# BTN.net
KiCad netlist of a schematic drawn in Altium Designer
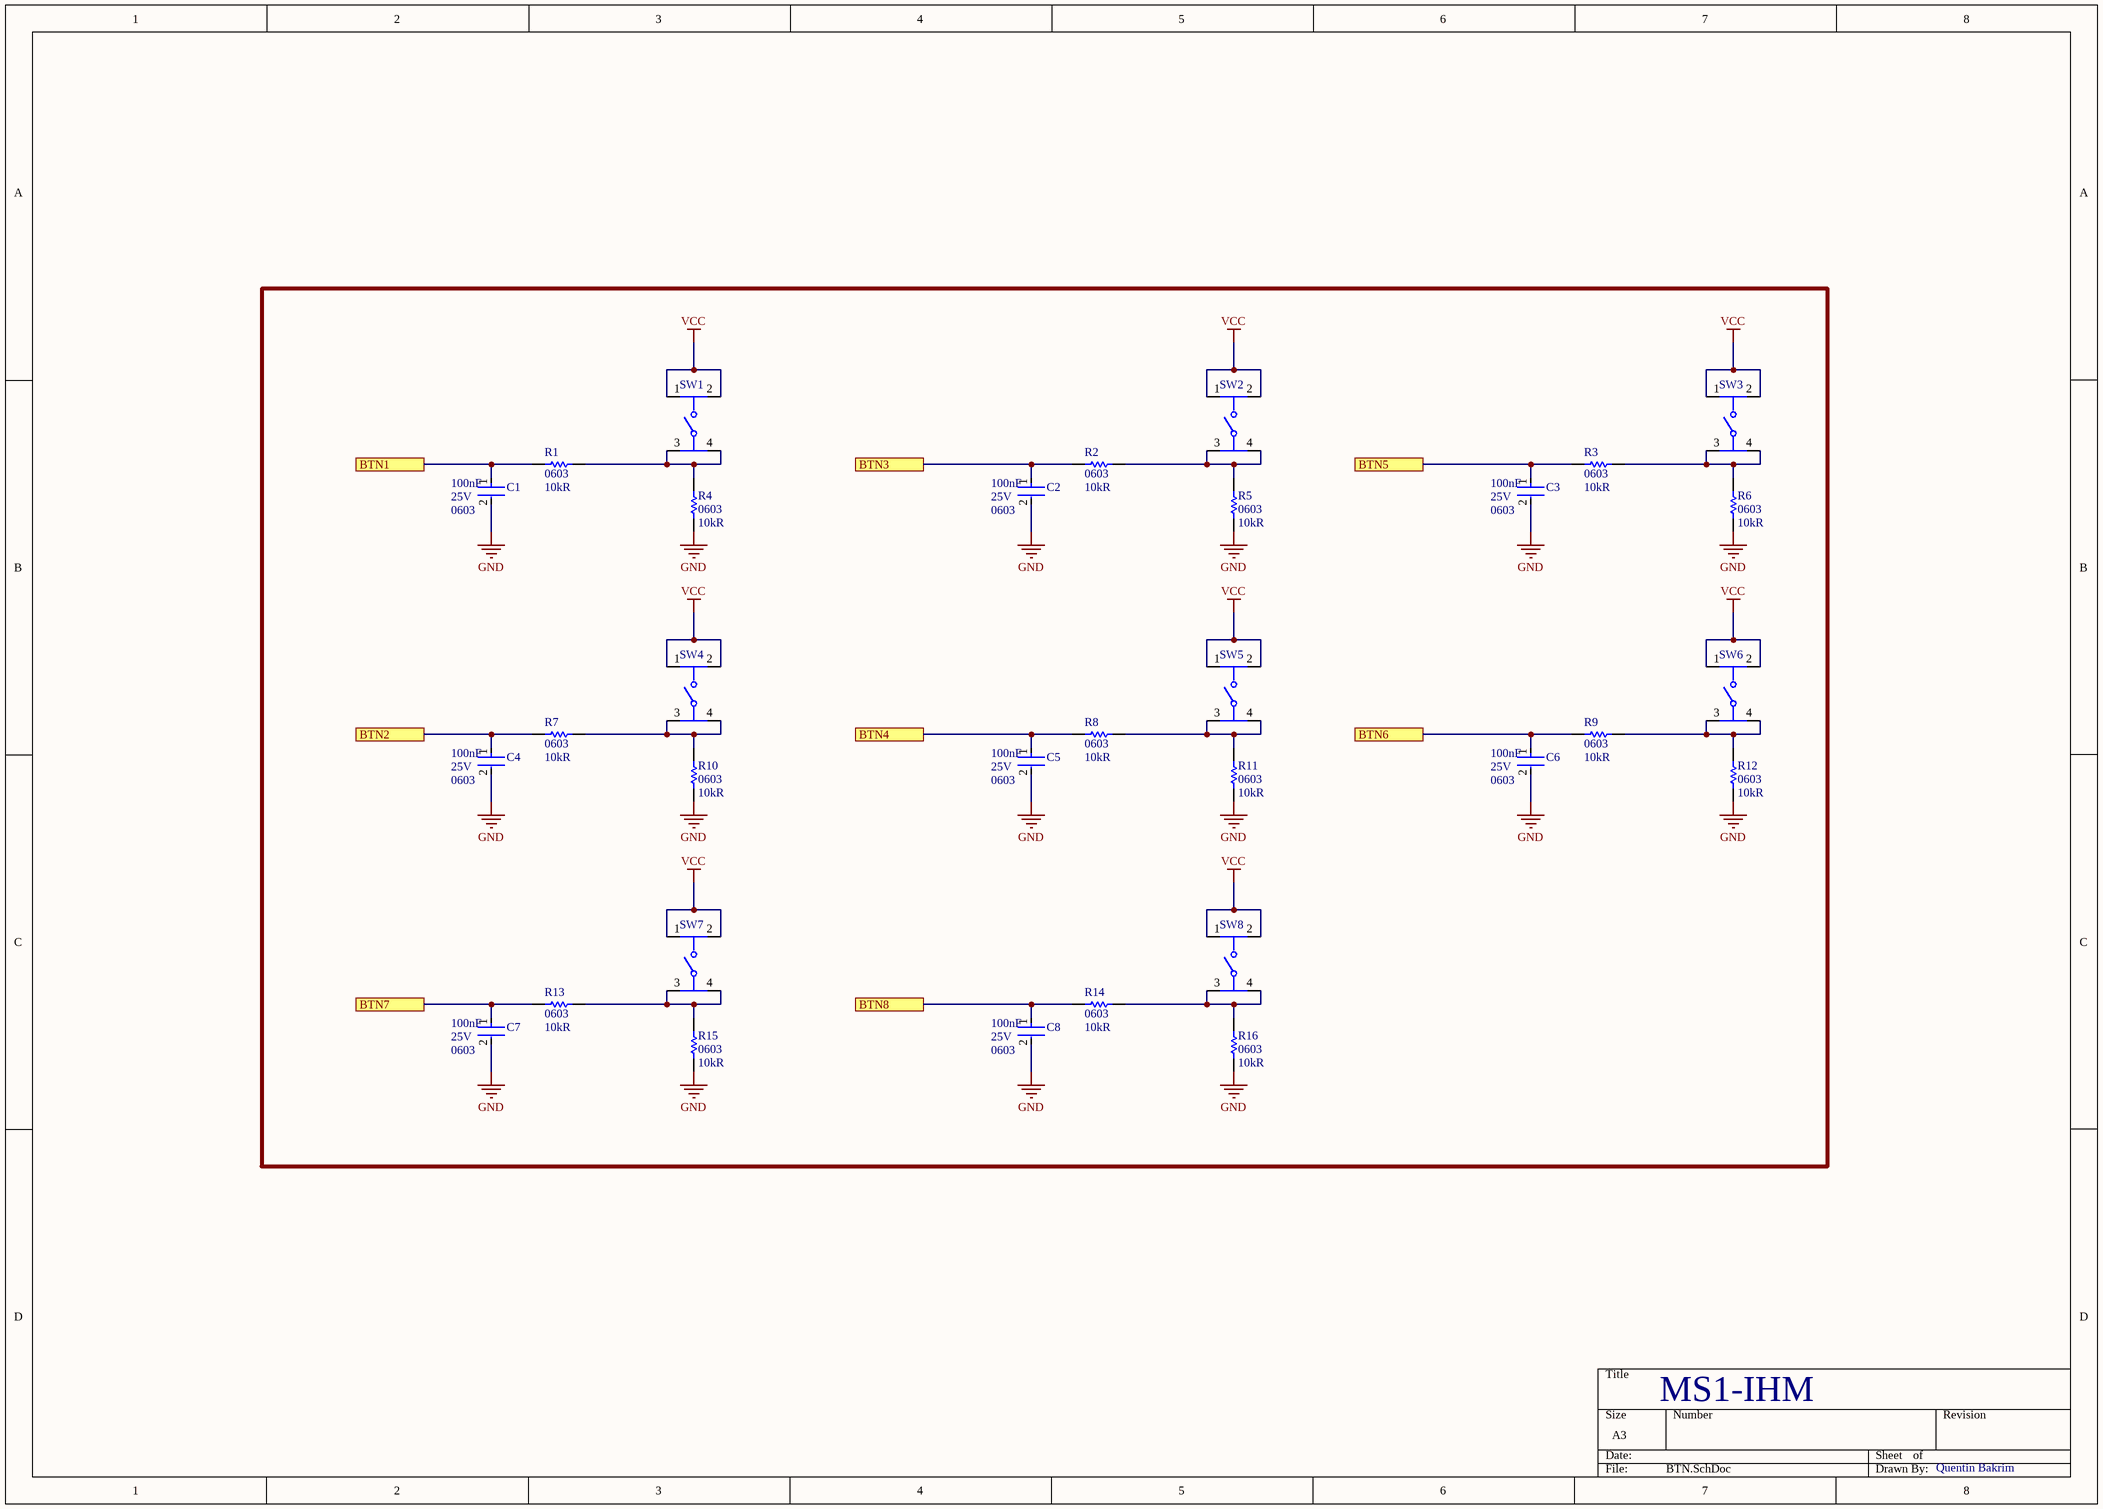
[diagram p0: BTN.SchDoc]

(export (version "E")
  (design (tool "Eeschema 10.0.6"))
  (components
    (comp (ref "C1")
      (value "CGA3E2X7R1E104K080AA")
      (footprint "FP-CGA3E-0_3-0_1-MFG")
      (description "Cap Ceramic 100nF 25V X7R 10% Pad SMD 0603 +125°C Automotive T/R")
      (fields
        (field (name "CASE/PACKAGE") "0603")
        (field (name "VOLTAGE RATING (DC)") "25V")
        (field (name "CAPACITANCE") "100nF")
        (field (name "TOLERANCE") "10%")
        (field (name "MANUFACTURER") "TDK")
      )
      (libsource (lib "Altium Content Vault") (part "b4654b650e69147ec39a6b967a45e02"))
    )
    (comp (ref "C2")
      (value "CGA3E2X7R1E104K080AA")
      (footprint "FP-CGA3E-0_3-0_1-MFG")
      (description "Cap Ceramic 100nF 25V X7R 10% Pad SMD 0603 +125°C Automotive T/R")
      (fields
        (field (name "CASE/PACKAGE") "0603")
        (field (name "VOLTAGE RATING (DC)") "25V")
        (field (name "CAPACITANCE") "100nF")
        (field (name "TOLERANCE") "10%")
        (field (name "MANUFACTURER") "TDK")
      )
      (libsource (lib "Altium Content Vault") (part "b4654b650e69147ec39a6b967a45e02"))
    )
    (comp (ref "C3")
      (value "CGA3E2X7R1E104K080AA")
      (footprint "FP-CGA3E-0_3-0_1-MFG")
      (description "Cap Ceramic 100nF 25V X7R 10% Pad SMD 0603 +125°C Automotive T/R")
      (fields
        (field (name "CASE/PACKAGE") "0603")
        (field (name "VOLTAGE RATING (DC)") "25V")
        (field (name "CAPACITANCE") "100nF")
        (field (name "TOLERANCE") "10%")
        (field (name "MANUFACTURER") "TDK")
      )
      (libsource (lib "Altium Content Vault") (part "b4654b650e69147ec39a6b967a45e02"))
    )
    (comp (ref "C4")
      (value "CGA3E2X7R1E104K080AA")
      (footprint "FP-CGA3E-0_3-0_1-MFG")
      (description "Cap Ceramic 100nF 25V X7R 10% Pad SMD 0603 +125°C Automotive T/R")
      (fields
        (field (name "CASE/PACKAGE") "0603")
        (field (name "VOLTAGE RATING (DC)") "25V")
        (field (name "CAPACITANCE") "100nF")
        (field (name "TOLERANCE") "10%")
        (field (name "MANUFACTURER") "TDK")
      )
      (libsource (lib "Altium Content Vault") (part "b4654b650e69147ec39a6b967a45e02"))
    )
    (comp (ref "C5")
      (value "CGA3E2X7R1E104K080AA")
      (footprint "FP-CGA3E-0_3-0_1-MFG")
      (description "Cap Ceramic 100nF 25V X7R 10% Pad SMD 0603 +125°C Automotive T/R")
      (fields
        (field (name "CASE/PACKAGE") "0603")
        (field (name "VOLTAGE RATING (DC)") "25V")
        (field (name "CAPACITANCE") "100nF")
        (field (name "TOLERANCE") "10%")
        (field (name "MANUFACTURER") "TDK")
      )
      (libsource (lib "Altium Content Vault") (part "b4654b650e69147ec39a6b967a45e02"))
    )
    (comp (ref "C6")
      (value "CGA3E2X7R1E104K080AA")
      (footprint "FP-CGA3E-0_3-0_1-MFG")
      (description "Cap Ceramic 100nF 25V X7R 10% Pad SMD 0603 +125°C Automotive T/R")
      (fields
        (field (name "CASE/PACKAGE") "0603")
        (field (name "VOLTAGE RATING (DC)") "25V")
        (field (name "CAPACITANCE") "100nF")
        (field (name "TOLERANCE") "10%")
        (field (name "MANUFACTURER") "TDK")
      )
      (libsource (lib "Altium Content Vault") (part "b4654b650e69147ec39a6b967a45e02"))
    )
    (comp (ref "C7")
      (value "CGA3E2X7R1E104K080AA")
      (footprint "FP-CGA3E-0_3-0_1-MFG")
      (description "Cap Ceramic 100nF 25V X7R 10% Pad SMD 0603 +125°C Automotive T/R")
      (fields
        (field (name "CASE/PACKAGE") "0603")
        (field (name "VOLTAGE RATING (DC)") "25V")
        (field (name "CAPACITANCE") "100nF")
        (field (name "TOLERANCE") "10%")
        (field (name "MANUFACTURER") "TDK")
      )
      (libsource (lib "Altium Content Vault") (part "b4654b650e69147ec39a6b967a45e02"))
    )
    (comp (ref "C8")
      (value "CGA3E2X7R1E104K080AA")
      (footprint "FP-CGA3E-0_3-0_1-MFG")
      (description "Cap Ceramic 100nF 25V X7R 10% Pad SMD 0603 +125°C Automotive T/R")
      (fields
        (field (name "CASE/PACKAGE") "0603")
        (field (name "VOLTAGE RATING (DC)") "25V")
        (field (name "CAPACITANCE") "100nF")
        (field (name "TOLERANCE") "10%")
        (field (name "MANUFACTURER") "TDK")
      )
      (libsource (lib "Altium Content Vault") (part "b4654b650e69147ec39a6b967a45e02"))
    )
    (comp (ref "R1")
      (value "ERJ3EKF1002V")
      (footprint "RESC1609X55X30LL15T15")
      (description "Chip Resistor, 10 KOhm, +/- 1%, 0.1 W, -55 to 155 degC, 0603 (1608 Metric), RoHS, Tape and Reel")
      (fields
        (field (name "CAS~{E}/PACKAGE") "0603")
        (field (name "RESISTANCE") "10kR")
        (field (name "TOLERANCE") "1%")
        (field (name "MANUFACTURER") "Panasonic")
      )
      (libsource (lib "Altium Content Vault") (part "RES-2"))
    )
    (comp (ref "R2")
      (value "ERJ3EKF1002V")
      (footprint "RESC1609X55X30LL15T15")
      (description "Chip Resistor, 10 KOhm, +/- 1%, 0.1 W, -55 to 155 degC, 0603 (1608 Metric), RoHS, Tape and Reel")
      (fields
        (field (name "CAS~{E}/PACKAGE") "0603")
        (field (name "RESISTANCE") "10kR")
        (field (name "TOLERANCE") "1%")
        (field (name "MANUFACTURER") "Panasonic")
      )
      (libsource (lib "Altium Content Vault") (part "RES-2"))
    )
    (comp (ref "R3")
      (value "ERJ3EKF1002V")
      (footprint "RESC1609X55X30LL15T15")
      (description "Chip Resistor, 10 KOhm, +/- 1%, 0.1 W, -55 to 155 degC, 0603 (1608 Metric), RoHS, Tape and Reel")
      (fields
        (field (name "CAS~{E}/PACKAGE") "0603")
        (field (name "RESISTANCE") "10kR")
        (field (name "TOLERANCE") "1%")
        (field (name "MANUFACTURER") "Panasonic")
      )
      (libsource (lib "Altium Content Vault") (part "RES-2"))
    )
    (comp (ref "R4")
      (value "ERJ3EKF1002V")
      (footprint "RESC1609X55X30LL15T15")
      (description "Chip Resistor, 10 KOhm, +/- 1%, 0.1 W, -55 to 155 degC, 0603 (1608 Metric), RoHS, Tape and Reel")
      (fields
        (field (name "CAS~{E}/PACKAGE") "0603")
        (field (name "RESISTANCE") "10kR")
        (field (name "TOLERANCE") "1%")
        (field (name "MANUFACTURER") "Panasonic")
      )
      (libsource (lib "Altium Content Vault") (part "RES-2"))
    )
    (comp (ref "R5")
      (value "ERJ3EKF1002V")
      (footprint "RESC1609X55X30LL15T15")
      (description "Chip Resistor, 10 KOhm, +/- 1%, 0.1 W, -55 to 155 degC, 0603 (1608 Metric), RoHS, Tape and Reel")
      (fields
        (field (name "CAS~{E}/PACKAGE") "0603")
        (field (name "RESISTANCE") "10kR")
        (field (name "TOLERANCE") "1%")
        (field (name "MANUFACTURER") "Panasonic")
      )
      (libsource (lib "Altium Content Vault") (part "RES-2"))
    )
    (comp (ref "R6")
      (value "ERJ3EKF1002V")
      (footprint "RESC1609X55X30LL15T15")
      (description "Chip Resistor, 10 KOhm, +/- 1%, 0.1 W, -55 to 155 degC, 0603 (1608 Metric), RoHS, Tape and Reel")
      (fields
        (field (name "CAS~{E}/PACKAGE") "0603")
        (field (name "RESISTANCE") "10kR")
        (field (name "TOLERANCE") "1%")
        (field (name "MANUFACTURER") "Panasonic")
      )
      (libsource (lib "Altium Content Vault") (part "RES-2"))
    )
    (comp (ref "R7")
      (value "ERJ3EKF1002V")
      (footprint "RESC1609X55X30LL15T15")
      (description "Chip Resistor, 10 KOhm, +/- 1%, 0.1 W, -55 to 155 degC, 0603 (1608 Metric), RoHS, Tape and Reel")
      (fields
        (field (name "CAS~{E}/PACKAGE") "0603")
        (field (name "RESISTANCE") "10kR")
        (field (name "TOLERANCE") "1%")
        (field (name "MANUFACTURER") "Panasonic")
      )
      (libsource (lib "Altium Content Vault") (part "RES-2"))
    )
    (comp (ref "R8")
      (value "ERJ3EKF1002V")
      (footprint "RESC1609X55X30LL15T15")
      (description "Chip Resistor, 10 KOhm, +/- 1%, 0.1 W, -55 to 155 degC, 0603 (1608 Metric), RoHS, Tape and Reel")
      (fields
        (field (name "CAS~{E}/PACKAGE") "0603")
        (field (name "RESISTANCE") "10kR")
        (field (name "TOLERANCE") "1%")
        (field (name "MANUFACTURER") "Panasonic")
      )
      (libsource (lib "Altium Content Vault") (part "RES-2"))
    )
    (comp (ref "R9")
      (value "ERJ3EKF1002V")
      (footprint "RESC1609X55X30LL15T15")
      (description "Chip Resistor, 10 KOhm, +/- 1%, 0.1 W, -55 to 155 degC, 0603 (1608 Metric), RoHS, Tape and Reel")
      (fields
        (field (name "CAS~{E}/PACKAGE") "0603")
        (field (name "RESISTANCE") "10kR")
        (field (name "TOLERANCE") "1%")
        (field (name "MANUFACTURER") "Panasonic")
      )
      (libsource (lib "Altium Content Vault") (part "RES-2"))
    )
    (comp (ref "R10")
      (value "ERJ3EKF1002V")
      (footprint "RESC1609X55X30LL15T15")
      (description "Chip Resistor, 10 KOhm, +/- 1%, 0.1 W, -55 to 155 degC, 0603 (1608 Metric), RoHS, Tape and Reel")
      (fields
        (field (name "CAS~{E}/PACKAGE") "0603")
        (field (name "RESISTANCE") "10kR")
        (field (name "TOLERANCE") "1%")
        (field (name "MANUFACTURER") "Panasonic")
      )
      (libsource (lib "Altium Content Vault") (part "RES-2"))
    )
    (comp (ref "R11")
      (value "ERJ3EKF1002V")
      (footprint "RESC1609X55X30LL15T15")
      (description "Chip Resistor, 10 KOhm, +/- 1%, 0.1 W, -55 to 155 degC, 0603 (1608 Metric), RoHS, Tape and Reel")
      (fields
        (field (name "CAS~{E}/PACKAGE") "0603")
        (field (name "RESISTANCE") "10kR")
        (field (name "TOLERANCE") "1%")
        (field (name "MANUFACTURER") "Panasonic")
      )
      (libsource (lib "Altium Content Vault") (part "RES-2"))
    )
    (comp (ref "R12")
      (value "ERJ3EKF1002V")
      (footprint "RESC1609X55X30LL15T15")
      (description "Chip Resistor, 10 KOhm, +/- 1%, 0.1 W, -55 to 155 degC, 0603 (1608 Metric), RoHS, Tape and Reel")
      (fields
        (field (name "CAS~{E}/PACKAGE") "0603")
        (field (name "RESISTANCE") "10kR")
        (field (name "TOLERANCE") "1%")
        (field (name "MANUFACTURER") "Panasonic")
      )
      (libsource (lib "Altium Content Vault") (part "RES-2"))
    )
    (comp (ref "R13")
      (value "ERJ3EKF1002V")
      (footprint "RESC1609X55X30LL15T15")
      (description "Chip Resistor, 10 KOhm, +/- 1%, 0.1 W, -55 to 155 degC, 0603 (1608 Metric), RoHS, Tape and Reel")
      (fields
        (field (name "CAS~{E}/PACKAGE") "0603")
        (field (name "RESISTANCE") "10kR")
        (field (name "TOLERANCE") "1%")
        (field (name "MANUFACTURER") "Panasonic")
      )
      (libsource (lib "Altium Content Vault") (part "RES-2"))
    )
    (comp (ref "R14")
      (value "ERJ3EKF1002V")
      (footprint "RESC1609X55X30LL15T15")
      (description "Chip Resistor, 10 KOhm, +/- 1%, 0.1 W, -55 to 155 degC, 0603 (1608 Metric), RoHS, Tape and Reel")
      (fields
        (field (name "CAS~{E}/PACKAGE") "0603")
        (field (name "RESISTANCE") "10kR")
        (field (name "TOLERANCE") "1%")
        (field (name "MANUFACTURER") "Panasonic")
      )
      (libsource (lib "Altium Content Vault") (part "RES-2"))
    )
    (comp (ref "R15")
      (value "ERJ3EKF1002V")
      (footprint "RESC1609X55X30LL15T15")
      (description "Chip Resistor, 10 KOhm, +/- 1%, 0.1 W, -55 to 155 degC, 0603 (1608 Metric), RoHS, Tape and Reel")
      (fields
        (field (name "CAS~{E}/PACKAGE") "0603")
        (field (name "RESISTANCE") "10kR")
        (field (name "TOLERANCE") "1%")
        (field (name "MANUFACTURER") "Panasonic")
      )
      (libsource (lib "Altium Content Vault") (part "RES-2"))
    )
    (comp (ref "R16")
      (value "ERJ3EKF1002V")
      (footprint "RESC1609X55X30LL15T15")
      (description "Chip Resistor, 10 KOhm, +/- 1%, 0.1 W, -55 to 155 degC, 0603 (1608 Metric), RoHS, Tape and Reel")
      (fields
        (field (name "CAS~{E}/PACKAGE") "0603")
        (field (name "RESISTANCE") "10kR")
        (field (name "TOLERANCE") "1%")
        (field (name "MANUFACTURER") "Panasonic")
      )
      (libsource (lib "Altium Content Vault") (part "RES-2"))
    )
    (comp (ref "SW1")
      (value "PTS645SM43SMTR92LFS")
      (footprint "FP-PTS645SM43SMTR92LFS-MFG")
      (libsource (lib "Altium Content Vault") (part "1adf0dd01260c80cf25a44bfd6b99ba"))
    )
    (comp (ref "SW2")
      (value "PTS645SM43SMTR92LFS")
      (footprint "FP-PTS645SM43SMTR92LFS-MFG")
      (libsource (lib "Altium Content Vault") (part "1adf0dd01260c80cf25a44bfd6b99ba"))
    )
    (comp (ref "SW3")
      (value "PTS645SM43SMTR92LFS")
      (footprint "FP-PTS645SM43SMTR92LFS-MFG")
      (libsource (lib "Altium Content Vault") (part "1adf0dd01260c80cf25a44bfd6b99ba"))
    )
    (comp (ref "SW4")
      (value "PTS645SM43SMTR92LFS")
      (footprint "FP-PTS645SM43SMTR92LFS-MFG")
      (libsource (lib "Altium Content Vault") (part "1adf0dd01260c80cf25a44bfd6b99ba"))
    )
    (comp (ref "SW5")
      (value "PTS645SM43SMTR92LFS")
      (footprint "FP-PTS645SM43SMTR92LFS-MFG")
      (libsource (lib "Altium Content Vault") (part "1adf0dd01260c80cf25a44bfd6b99ba"))
    )
    (comp (ref "SW6")
      (value "PTS645SM43SMTR92LFS")
      (footprint "FP-PTS645SM43SMTR92LFS-MFG")
      (libsource (lib "Altium Content Vault") (part "1adf0dd01260c80cf25a44bfd6b99ba"))
    )
    (comp (ref "SW7")
      (value "PTS645SM43SMTR92LFS")
      (footprint "FP-PTS645SM43SMTR92LFS-MFG")
      (libsource (lib "Altium Content Vault") (part "1adf0dd01260c80cf25a44bfd6b99ba"))
    )
    (comp (ref "SW8")
      (value "PTS645SM43SMTR92LFS")
      (footprint "FP-PTS645SM43SMTR92LFS-MFG")
      (libsource (lib "Altium Content Vault") (part "1adf0dd01260c80cf25a44bfd6b99ba"))
    )
  )
  (nets
    (net (code "1") (name "/BTN1") (class "Default")
      (node (ref "C1") (pin "1") (pinfunction "1_1") (pintype "passive"))
      (node (ref "R1") (pin "2") (pinfunction "2_2") (pintype "passive"))
    )
    (net (code "2") (name "/BTN2") (class "Default")
      (node (ref "C4") (pin "1") (pinfunction "1_1") (pintype "passive"))
      (node (ref "R7") (pin "2") (pinfunction "2_2") (pintype "passive"))
    )
    (net (code "3") (name "/BTN3") (class "Default")
      (node (ref "C2") (pin "1") (pinfunction "1_1") (pintype "passive"))
      (node (ref "R2") (pin "2") (pinfunction "2_2") (pintype "passive"))
    )
    (net (code "4") (name "/BTN4") (class "Default")
      (node (ref "C5") (pin "1") (pinfunction "1_1") (pintype "passive"))
      (node (ref "R8") (pin "2") (pinfunction "2_2") (pintype "passive"))
    )
    (net (code "5") (name "/BTN5") (class "Default")
      (node (ref "C3") (pin "1") (pinfunction "1_1") (pintype "passive"))
      (node (ref "R3") (pin "2") (pinfunction "2_2") (pintype "passive"))
    )
    (net (code "6") (name "/BTN6") (class "Default")
      (node (ref "C6") (pin "1") (pinfunction "1_1") (pintype "passive"))
      (node (ref "R9") (pin "2") (pinfunction "2_2") (pintype "passive"))
    )
    (net (code "7") (name "/BTN7") (class "Default")
      (node (ref "C7") (pin "1") (pinfunction "1_1") (pintype "passive"))
      (node (ref "R13") (pin "2") (pinfunction "2_2") (pintype "passive"))
    )
    (net (code "8") (name "/BTN8") (class "Default")
      (node (ref "C8") (pin "1") (pinfunction "1_1") (pintype "passive"))
      (node (ref "R14") (pin "2") (pinfunction "2_2") (pintype "passive"))
    )
    (net (code "9") (name "GND") (class "Default")
      (node (ref "C1") (pin "2") (pinfunction "2_2") (pintype "passive"))
      (node (ref "C2") (pin "2") (pinfunction "2_2") (pintype "passive"))
      (node (ref "C3") (pin "2") (pinfunction "2_2") (pintype "passive"))
      (node (ref "C4") (pin "2") (pinfunction "2_2") (pintype "passive"))
      (node (ref "C5") (pin "2") (pinfunction "2_2") (pintype "passive"))
      (node (ref "C6") (pin "2") (pinfunction "2_2") (pintype "passive"))
      (node (ref "C7") (pin "2") (pinfunction "2_2") (pintype "passive"))
      (node (ref "C8") (pin "2") (pinfunction "2_2") (pintype "passive"))
      (node (ref "R10") (pin "1") (pinfunction "1_1") (pintype "passive"))
      (node (ref "R11") (pin "1") (pinfunction "1_1") (pintype "passive"))
      (node (ref "R12") (pin "1") (pinfunction "1_1") (pintype "passive"))
      (node (ref "R15") (pin "1") (pinfunction "1_1") (pintype "passive"))
      (node (ref "R16") (pin "1") (pinfunction "1_1") (pintype "passive"))
      (node (ref "R4") (pin "1") (pinfunction "1_1") (pintype "passive"))
      (node (ref "R5") (pin "1") (pinfunction "1_1") (pintype "passive"))
      (node (ref "R6") (pin "1") (pinfunction "1_1") (pintype "passive"))
    )
    (net (code "10") (name "Net-(R1-Pad1)") (class "Default")
      (node (ref "R1") (pin "1") (pinfunction "1_1") (pintype "passive"))
      (node (ref "R4") (pin "2") (pinfunction "2_2") (pintype "passive"))
      (node (ref "SW1") (pin "3") (pinfunction "3_3") (pintype "passive"))
      (node (ref "SW1") (pin "4") (pinfunction "4_4") (pintype "passive"))
    )
    (net (code "11") (name "Net-(R2-Pad1)") (class "Default")
      (node (ref "R2") (pin "1") (pinfunction "1_1") (pintype "passive"))
      (node (ref "R5") (pin "2") (pinfunction "2_2") (pintype "passive"))
      (node (ref "SW2") (pin "3") (pinfunction "3_3") (pintype "passive"))
      (node (ref "SW2") (pin "4") (pinfunction "4_4") (pintype "passive"))
    )
    (net (code "12") (name "Net-(R3-Pad1)") (class "Default")
      (node (ref "R3") (pin "1") (pinfunction "1_1") (pintype "passive"))
      (node (ref "R6") (pin "2") (pinfunction "2_2") (pintype "passive"))
      (node (ref "SW3") (pin "3") (pinfunction "3_3") (pintype "passive"))
      (node (ref "SW3") (pin "4") (pinfunction "4_4") (pintype "passive"))
    )
    (net (code "13") (name "Net-(R10-Pad2)") (class "Default")
      (node (ref "R10") (pin "2") (pinfunction "2_2") (pintype "passive"))
      (node (ref "R7") (pin "1") (pinfunction "1_1") (pintype "passive"))
      (node (ref "SW4") (pin "3") (pinfunction "3_3") (pintype "passive"))
      (node (ref "SW4") (pin "4") (pinfunction "4_4") (pintype "passive"))
    )
    (net (code "14") (name "Net-(R11-Pad2)") (class "Default")
      (node (ref "R11") (pin "2") (pinfunction "2_2") (pintype "passive"))
      (node (ref "R8") (pin "1") (pinfunction "1_1") (pintype "passive"))
      (node (ref "SW5") (pin "3") (pinfunction "3_3") (pintype "passive"))
      (node (ref "SW5") (pin "4") (pinfunction "4_4") (pintype "passive"))
    )
    (net (code "15") (name "Net-(R12-Pad2)") (class "Default")
      (node (ref "R12") (pin "2") (pinfunction "2_2") (pintype "passive"))
      (node (ref "R9") (pin "1") (pinfunction "1_1") (pintype "passive"))
      (node (ref "SW6") (pin "3") (pinfunction "3_3") (pintype "passive"))
      (node (ref "SW6") (pin "4") (pinfunction "4_4") (pintype "passive"))
    )
    (net (code "16") (name "Net-(R13-Pad1)") (class "Default")
      (node (ref "R13") (pin "1") (pinfunction "1_1") (pintype "passive"))
      (node (ref "R15") (pin "2") (pinfunction "2_2") (pintype "passive"))
      (node (ref "SW7") (pin "3") (pinfunction "3_3") (pintype "passive"))
      (node (ref "SW7") (pin "4") (pinfunction "4_4") (pintype "passive"))
    )
    (net (code "17") (name "Net-(R14-Pad1)") (class "Default")
      (node (ref "R14") (pin "1") (pinfunction "1_1") (pintype "passive"))
      (node (ref "R16") (pin "2") (pinfunction "2_2") (pintype "passive"))
      (node (ref "SW8") (pin "3") (pinfunction "3_3") (pintype "passive"))
      (node (ref "SW8") (pin "4") (pinfunction "4_4") (pintype "passive"))
    )
    (net (code "18") (name "VCC") (class "Default")
      (node (ref "SW1") (pin "1") (pinfunction "1_1") (pintype "passive"))
      (node (ref "SW1") (pin "2") (pinfunction "2_2") (pintype "passive"))
      (node (ref "SW2") (pin "1") (pinfunction "1_1") (pintype "passive"))
      (node (ref "SW2") (pin "2") (pinfunction "2_2") (pintype "passive"))
      (node (ref "SW3") (pin "1") (pinfunction "1_1") (pintype "passive"))
      (node (ref "SW3") (pin "2") (pinfunction "2_2") (pintype "passive"))
      (node (ref "SW4") (pin "1") (pinfunction "1_1") (pintype "passive"))
      (node (ref "SW4") (pin "2") (pinfunction "2_2") (pintype "passive"))
      (node (ref "SW5") (pin "1") (pinfunction "1_1") (pintype "passive"))
      (node (ref "SW5") (pin "2") (pinfunction "2_2") (pintype "passive"))
      (node (ref "SW6") (pin "1") (pinfunction "1_1") (pintype "passive"))
      (node (ref "SW6") (pin "2") (pinfunction "2_2") (pintype "passive"))
      (node (ref "SW7") (pin "1") (pinfunction "1_1") (pintype "passive"))
      (node (ref "SW7") (pin "2") (pinfunction "2_2") (pintype "passive"))
      (node (ref "SW8") (pin "1") (pinfunction "1_1") (pintype "passive"))
      (node (ref "SW8") (pin "2") (pinfunction "2_2") (pintype "passive"))
    )
  )
)
